# PISCES_200.net
KiCad netlist of a schematic drawn in Altium Designer
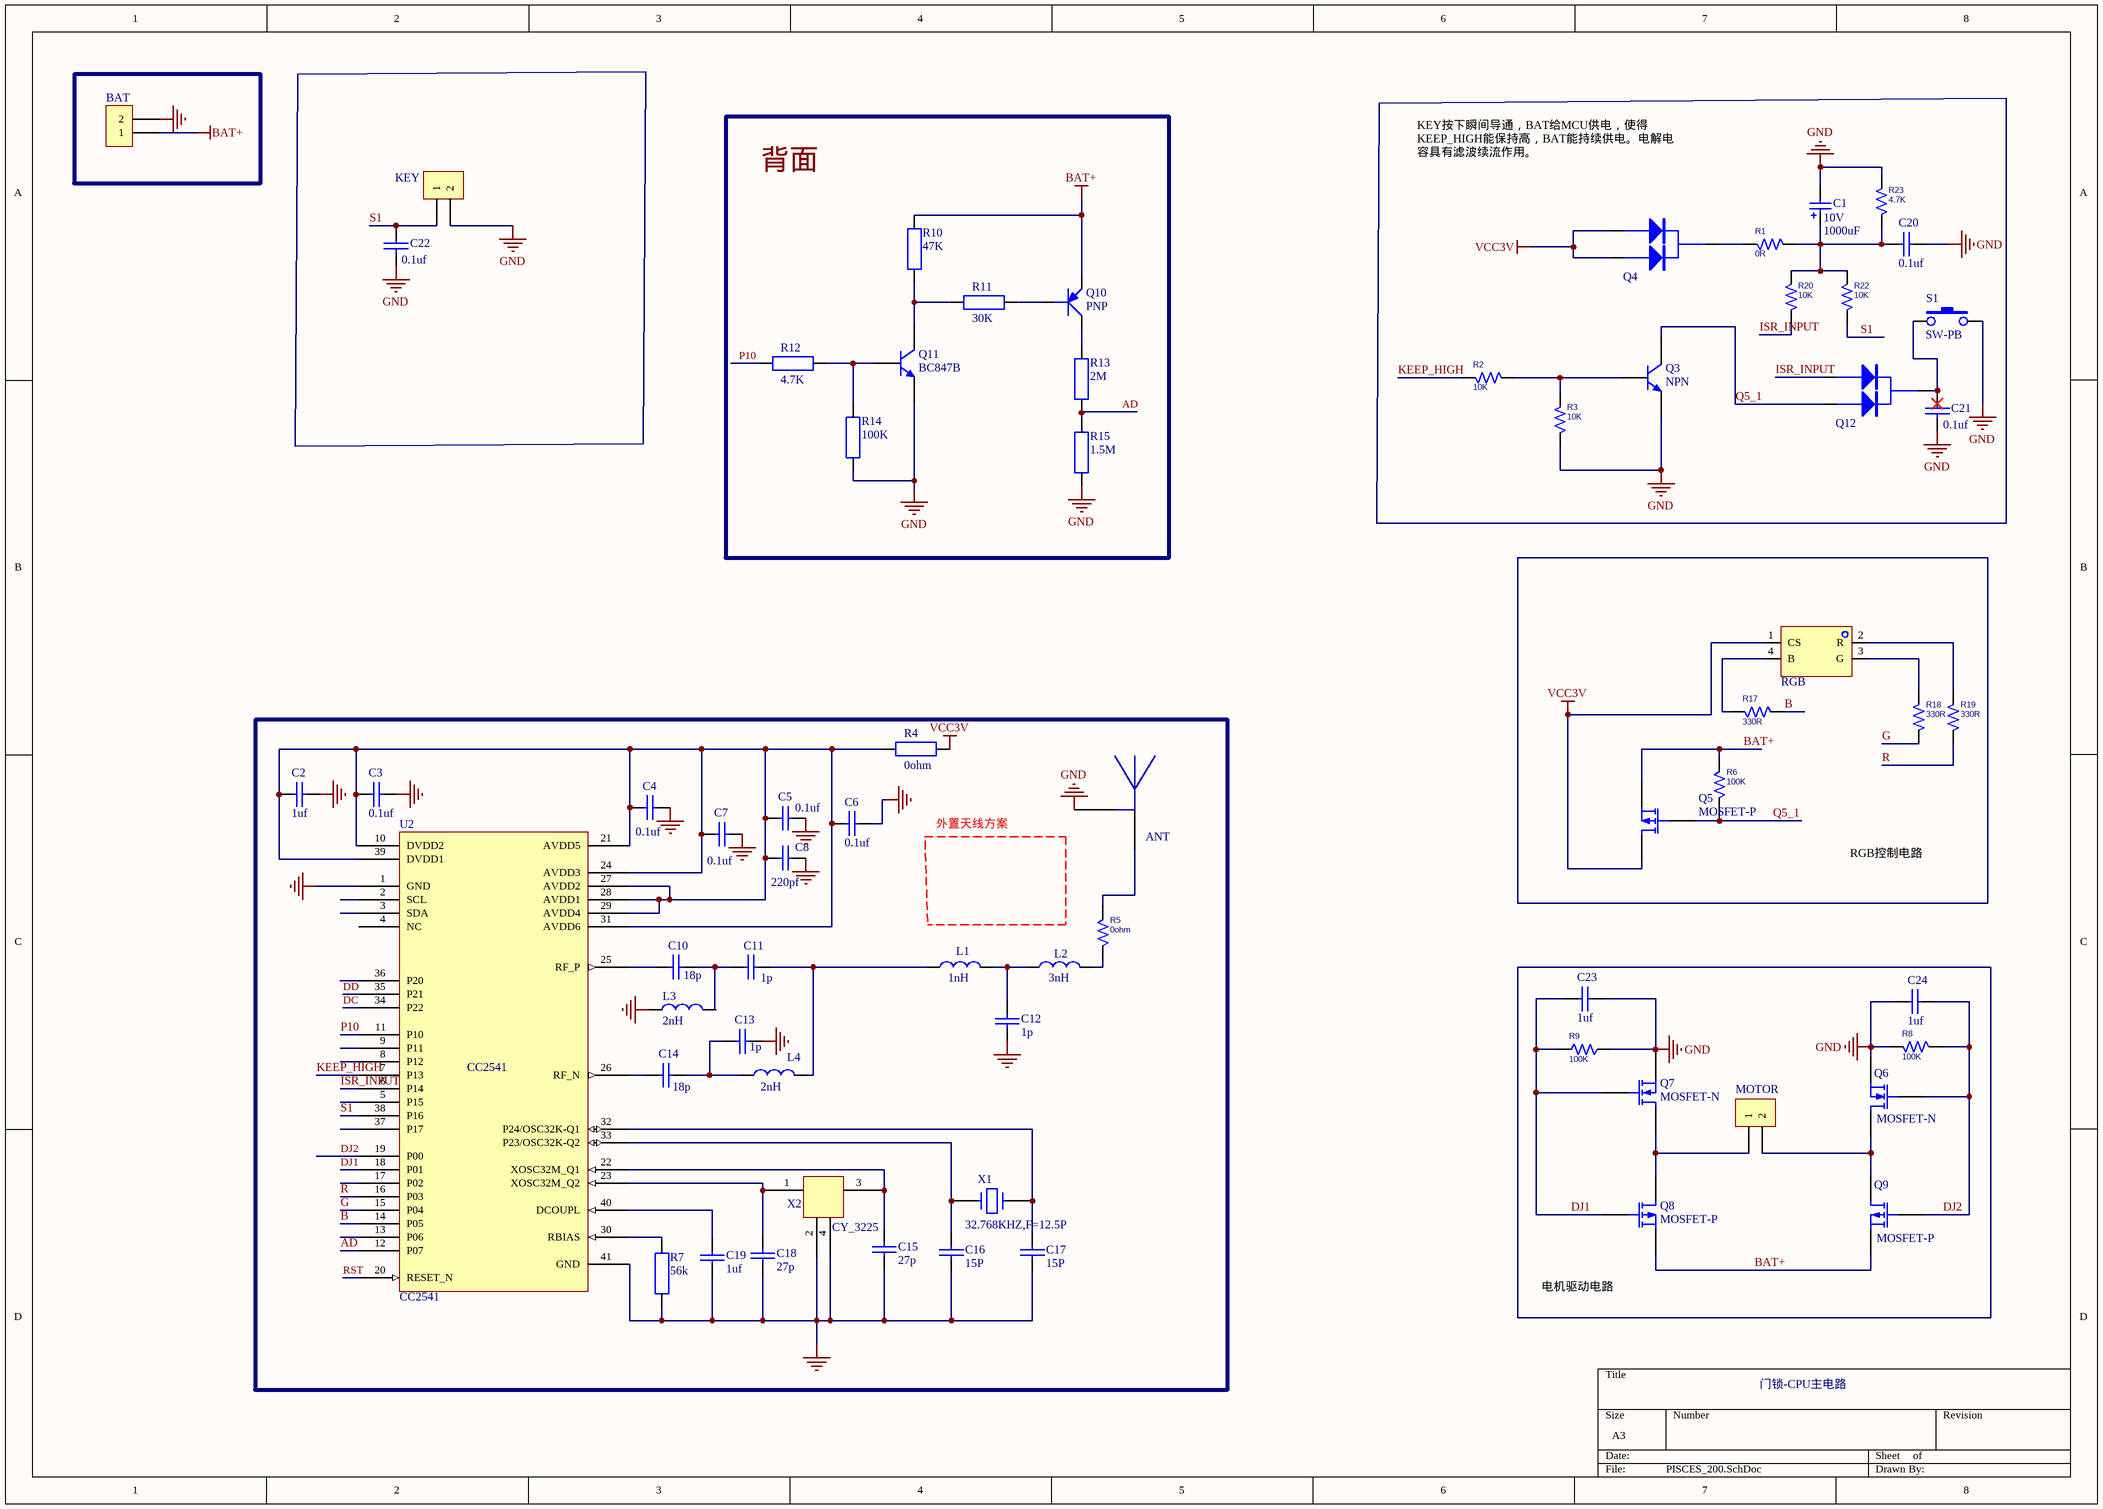
[diagram p0: PISCES_200.SchDoc]

(export (version "E")
  (design (tool "Eeschema 10.0.6"))
  (components
    (comp (ref "ANT") (value "ANT") (footprint "ANT") (libsource (lib "BT100_Project") (part "ANT")))
    (comp (ref "BAT")
      (value "CN1")
      (footprint "2PAD")
      (description "Connector")
      (libsource (lib "") (part "CON2_1"))
    )
    (comp (ref "C1")
      (value "10V")
      (footprint "CAT_ELE")
      (description "Polarized Capacitor (Axial)")
      (fields (field (name "ALTIUM_VALUE") "1000uF") (field (name "PUBLISHER") "Altium Limited"))
      (libsource (lib "Miscellaneous Devices") (part "Cap Pol2"))
    )
    (comp (ref "C2")
      (value "1uf")
      (footprint "PC5-*****-**-0A_0603_TDK")
      (description "PC7-*****-KQA0A")
      (libsource (lib "Schlib") (part "PC7_0402_YAGEO"))
    )
    (comp (ref "C3")
      (value "0.1uf")
      (footprint "PC5-*****-**-0A_0603_TDK")
      (description "PC7-*****-KQA0A")
      (libsource (lib "Schlib") (part "PC7_0402_YAGEO"))
    )
    (comp (ref "C4")
      (value "0.1uf")
      (footprint "PC5-*****-**-0A_0603_TDK")
      (description "PC7-*****-KQA0A")
      (libsource (lib "Schlib") (part "PC7_0402_YAGEO"))
    )
    (comp (ref "C5")
      (value "0.1uf")
      (footprint "PC7-*****-KQA0A_0402_YAGEO")
      (description "PC7-*****-KQA0A")
      (libsource (lib "Schlib") (part "PC7_0402_YAGEO"))
    )
    (comp (ref "C6")
      (value "0.1uf")
      (footprint "PC7-*****-KQA0A_0402_YAGEO")
      (description "PC7-*****-KQA0A")
      (libsource (lib "Schlib") (part "PC7_0402_YAGEO"))
    )
    (comp (ref "C7")
      (value "0.1uf")
      (footprint "PC7-*****-KQA0A_0402_YAGEO")
      (description "PC7-*****-KQA0A")
      (libsource (lib "Schlib") (part "PC7_0402_YAGEO"))
    )
    (comp (ref "C8")
      (value "220pf")
      (footprint "PC7-*****-KQA0A_0402_YAGEO")
      (description "PC7-*****-KQA0A")
      (libsource (lib "Schlib") (part "PC7_0402_YAGEO"))
    )
    (comp (ref "C10")
      (value "18p")
      (footprint "PC7-*****-KQA0A_0402_YAGEO")
      (description "PC7-*****-KQA0A")
      (libsource (lib "Schlib") (part "PC7_0402_YAGEO"))
    )
    (comp (ref "C11")
      (value "1p")
      (footprint "PC7-*****-KQA0A_0402_YAGEO")
      (description "PC7-*****-KQA0A")
      (libsource (lib "Schlib") (part "PC7_0402_YAGEO"))
    )
    (comp (ref "C12")
      (value "1p")
      (footprint "PC7-*****-KQA0A_0402_YAGEO")
      (description "PC7-*****-KQA0A")
      (libsource (lib "Schlib") (part "PC7_0402_YAGEO"))
    )
    (comp (ref "C13")
      (value "1p")
      (footprint "PC7-*****-KQA0A_0402_YAGEO")
      (description "PC7-*****-KQA0A")
      (libsource (lib "Schlib") (part "PC7_0402_YAGEO"))
    )
    (comp (ref "C14")
      (value "18p")
      (footprint "PC7-*****-KQA0A_0402_YAGEO")
      (description "PC7-*****-KQA0A")
      (libsource (lib "Schlib") (part "PC7_0402_YAGEO"))
    )
    (comp (ref "C15")
      (value "27p")
      (footprint "PC7-*****-KO-0A_0603_TDK")
      (description "PC7-*****-KQA0A")
      (libsource (lib "Schlib") (part "PC7_0402_YAGEO"))
    )
    (comp (ref "C16")
      (value "15P")
      (footprint "PC5-*****-**-0A_0603_TDK")
      (description "PC7-*****-KQA0A")
      (libsource (lib "Schlib") (part "PC7_0402_YAGEO"))
    )
    (comp (ref "C17")
      (value "15P")
      (footprint "PC7-*****-KO-0A_0603_TDK")
      (description "PC7-*****-KQA0A")
      (libsource (lib "Schlib") (part "PC7_0402_YAGEO"))
    )
    (comp (ref "C18")
      (value "27p")
      (footprint "PC7-*****-KO-0A_0603_TDK")
      (description "PC7-*****-KQA0A")
      (libsource (lib "Schlib") (part "PC7_0402_YAGEO"))
    )
    (comp (ref "C19")
      (value "1uf")
      (footprint "PC5-*****-**-0A_0603_TDK")
      (description "PC7-*****-KQA0A")
      (libsource (lib "Schlib") (part "PC7_0402_YAGEO"))
    )
    (comp (ref "C20")
      (value "0.1uf")
      (footprint "PC7-*****-KQA0A_0402_YAGEO")
      (description "PC7-*****-KQA0A")
      (libsource (lib "Schlib") (part "PC7_0402_YAGEO"))
    )
    (comp (ref "C21")
      (value "0.1uf")
      (footprint "PC7-*****-KQA0A_0402_YAGEO")
      (description "PC7-*****-KQA0A")
      (libsource (lib "Schlib") (part "PC7_0402_YAGEO"))
    )
    (comp (ref "C22")
      (value "0.1uf")
      (footprint "PC7-*****-KQA0A_0402_YAGEO")
      (description "PC7-*****-KQA0A")
      (libsource (lib "Schlib") (part "PC7_0402_YAGEO"))
    )
    (comp (ref "C23")
      (value "1uf")
      (footprint "PC7-*****-KO-0A_0603_TDK")
      (description "PC7-*****-KQA0A")
      (libsource (lib "Schlib") (part "PC7_0402_YAGEO"))
    )
    (comp (ref "C24")
      (value "1uf")
      (footprint "PC7-*****-KO-0A_0603_TDK")
      (description "PC7-*****-KQA0A")
      (libsource (lib "Schlib") (part "PC7_0402_YAGEO"))
    )
    (comp (ref "KEY")
      (value "CN1")
      (footprint "KEY_2P")
      (description "Connector")
      (libsource (lib "BJC") (part "CON2"))
    )
    (comp (ref "L1")
      (value "1nH")
      (footprint "PC5-*****-**-0A_0402_TDK")
      (description "PWL-00195-00-20")
      (libsource (lib "Schlib") (part "PWL_18nH"))
    )
    (comp (ref "L2")
      (value "3nH")
      (footprint "PC5-*****-**-0A_0402_TDK")
      (description "PWL-00195-00-20")
      (libsource (lib "Schlib") (part "PWL_18nH"))
    )
    (comp (ref "L3")
      (value "2nH")
      (footprint "PC5-*****-**-0A_0402_TDK")
      (description "PWL-00195-00-20")
      (libsource (lib "Schlib") (part "PWL_18nH"))
    )
    (comp (ref "L4")
      (value "2nH")
      (footprint "PC5-*****-**-0A_0402_TDK")
      (description "PWL-00195-00-20")
      (libsource (lib "Schlib") (part "PWL_18nH"))
    )
    (comp (ref "MOTOR")
      (value "CN1")
      (footprint "2PAD")
      (description "Connector")
      (libsource (lib "BJC") (part "CON2"))
    )
    (comp (ref "Q3")
      (value "NPN")
      (footprint "SOT-23")
      (description "BC847C")
      (fields (field (name "PUBLISHER") "Altium Limited"))
      (libsource (lib "PISCES_200") (part "NPN"))
    )
    (comp (ref "Q4") (value "Q4") (footprint "SOT-23") (libsource (lib "PISCES_200") (part "BAT54C")))
    (comp (ref "Q5")
      (value "MOSFET-P")
      (footprint "SOT-23")
      (description "P-Channel MOSFET")
      (fields (field (name "PUBLISHER") "Altium Limited"))
      (libsource (lib "PISCES_200") (part "MOSFET-P"))
    )
    (comp (ref "Q6")
      (value "MOSFET-N")
      (footprint "SOT-23")
      (description "N-Channel MOSFET")
      (fields (field (name "PUBLISHER") "Altium Limited"))
      (libsource (lib "PISCES_200") (part "MOSFET-N"))
    )
    (comp (ref "Q7")
      (value "MOSFET-N")
      (footprint "SOT-23")
      (description "N-Channel MOSFET")
      (fields (field (name "PUBLISHER") "Altium Limited"))
      (libsource (lib "PISCES_200") (part "MOSFET-N"))
    )
    (comp (ref "Q8")
      (value "MOSFET-P")
      (footprint "SOT-23")
      (description "P-Channel MOSFET")
      (fields (field (name "PUBLISHER") "Altium Limited"))
      (libsource (lib "PISCES_200") (part "MOSFET-P"))
    )
    (comp (ref "Q9")
      (value "MOSFET-P")
      (footprint "SOT-23")
      (description "P-Channel MOSFET")
      (fields (field (name "PUBLISHER") "Altium Limited"))
      (libsource (lib "PISCES_200") (part "MOSFET-P"))
    )
    (comp (ref "Q10")
      (value "PNP")
      (footprint "SOT-23")
      (description "BC857C")
      (libsource (lib "PISCES_200") (part "PNP"))
    )
    (comp (ref "Q11")
      (value "BC847B")
      (footprint "SOT-23")
      (description "BC847C")
      (fields (field (name "PUBLISHER") "Altium Limited"))
      (libsource (lib "PISCES_200") (part "NPN"))
    )
    (comp (ref "Q12") (value "Q12") (footprint "SOT-23") (libsource (lib "PISCES_200") (part "BAT54C")))
    (comp (ref "R1")
      (value "0R")
      (footprint "PC7-*****-KQA0A_0402_YAGEO")
      (libsource (lib "*") (part "R_Dup3"))
    )
    (comp (ref "R2")
      (value "10K")
      (footprint "PC7-*****-KQA0A_0402_YAGEO")
      (libsource (lib "*") (part "R_Dup3"))
    )
    (comp (ref "R3")
      (value "10K")
      (footprint "PC7-*****-KQA0A_0402_YAGEO")
      (libsource (lib "*") (part "R_Dup3"))
    )
    (comp (ref "R4")
      (value "0ohm")
      (footprint "PC7-*****-KQA0A_0402_YAGEO")
      (description "PRC-*****-AM-0A_0603")
      (libsource (lib "Schlib") (part "PRC_0603"))
    )
    (comp (ref "R5")
      (value "0ohm")
      (footprint "PC7-*****-KQA0A_0402_YAGEO")
      (libsource (lib "*") (part "R_Dup3"))
    )
    (comp (ref "R6")
      (value "100K")
      (footprint "PC7-*****-KQA0A_0402_YAGEO")
      (libsource (lib "*") (part "R_Dup3"))
    )
    (comp (ref "R7")
      (value "56k")
      (footprint "PRC-*****-BM-0A_0402")
      (description "PRC-*****-AM-0A_0603")
      (libsource (lib "Schlib") (part "PRC_0603"))
    )
    (comp (ref "R8")
      (value "100K")
      (footprint "PC7-*****-KQA0A_0402_YAGEO")
      (libsource (lib "*") (part "R_Dup3"))
    )
    (comp (ref "R9")
      (value "100K")
      (footprint "PC7-*****-KQA0A_0402_YAGEO")
      (libsource (lib "*") (part "R_Dup3"))
    )
    (comp (ref "R10")
      (value "47K")
      (footprint "PISCES_200:PC7-*****-KQA0A_0402_YAGEO")
      (description "PRC-*****-AM-0A_0603")
      (libsource (lib "Schlib") (part "PRC_0603"))
    )
    (comp (ref "R11")
      (value "30K")
      (footprint "PISCES_200:PC7-*****-KQA0A_0402_YAGEO")
      (description "PRC-*****-AM-0A_0603")
      (libsource (lib "Schlib") (part "PRC_0603"))
    )
    (comp (ref "R12")
      (value "4.7K")
      (footprint "PISCES_200:PC7-*****-KQA0A_0402_YAGEO")
      (description "PRC-*****-AM-0A_0603")
      (libsource (lib "Schlib") (part "PRC_0603"))
    )
    (comp (ref "R13")
      (value "2M")
      (footprint "PISCES_200:PC7-*****-KQA0A_0402_YAGEO")
      (description "PRC-*****-AM-0A_0603")
      (libsource (lib "Schlib") (part "PRC_0603"))
    )
    (comp (ref "R14")
      (value "100K")
      (footprint "PISCES_200:PC7-*****-KQA0A_0402_YAGEO")
      (description "PRC-*****-AM-0A_0603")
      (libsource (lib "Schlib") (part "PRC_0603"))
    )
    (comp (ref "R15")
      (value "1.5M")
      (footprint "PISCES_200:PC7-*****-KQA0A_0402_YAGEO")
      (description "PRC-*****-AM-0A_0603")
      (libsource (lib "Schlib") (part "PRC_0603"))
    )
    (comp (ref "R17")
      (value "330R")
      (footprint "PC7-*****-KQA0A_0402_YAGEO")
      (libsource (lib "*") (part "R_Dup3"))
    )
    (comp (ref "R18")
      (value "330R")
      (footprint "PC7-*****-KQA0A_0402_YAGEO")
      (libsource (lib "*") (part "R_Dup3"))
    )
    (comp (ref "R19")
      (value "330R")
      (footprint "PC7-*****-KQA0A_0402_YAGEO")
      (libsource (lib "*") (part "R_Dup3"))
    )
    (comp (ref "R20")
      (value "10K")
      (footprint "PC7-*****-KQA0A_0402_YAGEO")
      (libsource (lib "*") (part "R_Dup3"))
    )
    (comp (ref "R22")
      (value "10K")
      (footprint "PC7-*****-KQA0A_0402_YAGEO")
      (libsource (lib "*") (part "R_Dup3"))
    )
    (comp (ref "R23")
      (value "4.7K")
      (footprint "PC7-*****-KQA0A_0402_YAGEO")
      (libsource (lib "*") (part "R_Dup3"))
    )
    (comp (ref "RGB") (value "RGB") (libsource (lib "PISCES_200") (part "RGB")))
    (comp (ref "S1") (value "SW-PB") (footprint "TS-030") (libsource (lib "LG_SCH") (part "SW-PB")))
    (comp (ref "U2") (value "CC2541") (footprint "CC2530_QFN40") (libsource (lib "*") (part "CC2541")))
    (comp (ref "X1")
      (value "32.768KHZ,F=12.5P")
      (footprint "FC-135")
      (description "Crystal")
      (libsource (lib "CC254xEM原理图库") (part "CRYSTAL"))
    )
    (comp (ref "X2")
      (value "CY_3225")
      (footprint "CY_3225")
      (libsource (lib "CC254xEM原理图库") (part "CY_3225"))
    )
  )
  (nets
    (net (code "1") (name "/AD") (class "Default")
      (node (ref "R13") (pin "1") (pinfunction "1_1") (pintype "passive"))
      (node (ref "R15") (pin "2") (pinfunction "2_2") (pintype "passive"))
      (node (ref "U2") (pin "12") (pinfunction "P07_12") (pintype "passive"))
    )
    (net (code "2") (name "/B") (class "Default")
      (node (ref "R17") (pin "2") (pinfunction "2_2") (pintype "passive"))
      (node (ref "U2") (pin "14") (pinfunction "P05_14") (pintype "passive"))
    )
    (net (code "3") (name "/DC") (class "Default")
      (node (ref "U2") (pin "34") (pinfunction "P22_34") (pintype "passive"))
    )
    (net (code "4") (name "/DD") (class "Default")
      (node (ref "U2") (pin "35") (pinfunction "P21_35") (pintype "passive"))
    )
    (net (code "5") (name "/DJ1") (class "Default")
      (node (ref "C23") (pin "1") (pinfunction "1_1") (pintype "passive"))
      (node (ref "Q7") (pin "1") (pinfunction "G_1") (pintype "passive"))
      (node (ref "Q8") (pin "1") (pinfunction "G_1") (pintype "passive"))
      (node (ref "R9") (pin "1") (pinfunction "1_1") (pintype "passive"))
      (node (ref "U2") (pin "18") (pinfunction "P01_18") (pintype "passive"))
    )
    (net (code "6") (name "/DJ2") (class "Default")
      (node (ref "C24") (pin "2") (pinfunction "2_2") (pintype "passive"))
      (node (ref "Q6") (pin "1") (pinfunction "G_1") (pintype "passive"))
      (node (ref "Q9") (pin "1") (pinfunction "G_1") (pintype "passive"))
      (node (ref "R8") (pin "1") (pinfunction "1_1") (pintype "passive"))
      (node (ref "U2") (pin "19") (pinfunction "P00_19") (pintype "passive"))
    )
    (net (code "7") (name "/G") (class "Default")
      (node (ref "R18") (pin "2") (pinfunction "2_2") (pintype "passive"))
      (node (ref "U2") (pin "15") (pinfunction "P04_15") (pintype "passive"))
    )
    (net (code "8") (name "/ISR_INPUT") (class "Default")
      (node (ref "Q12") (pin "1") (pinfunction "1_1") (pintype "passive"))
      (node (ref "R20") (pin "1") (pinfunction "1_1") (pintype "passive"))
      (node (ref "U2") (pin "6") (pinfunction "P14_6") (pintype "passive"))
    )
    (net (code "9") (name "/KEEP_HIGH") (class "Default")
      (node (ref "R2") (pin "1") (pinfunction "1_1") (pintype "passive"))
      (node (ref "U2") (pin "7") (pinfunction "P13_7") (pintype "passive"))
    )
    (net (code "10") (name "/P10") (class "Default")
      (node (ref "R12") (pin "1") (pinfunction "1_1") (pintype "passive"))
      (node (ref "U2") (pin "11") (pinfunction "P10_11") (pintype "passive"))
    )
    (net (code "11") (name "/Q5_1") (class "Default")
      (node (ref "Q12") (pin "2") (pinfunction "2_2") (pintype "passive"))
      (node (ref "Q3") (pin "3") (pinfunction "3_3") (pintype "passive"))
      (node (ref "Q5") (pin "1") (pinfunction "G_1") (pintype "passive"))
      (node (ref "R6") (pin "2") (pinfunction "2_2") (pintype "passive"))
    )
    (net (code "12") (name "/R") (class "Default")
      (node (ref "R19") (pin "2") (pinfunction "2_2") (pintype "passive"))
      (node (ref "U2") (pin "16") (pinfunction "P03_16") (pintype "passive"))
    )
    (net (code "13") (name "/RST") (class "Default")
      (node (ref "U2") (pin "20") (pinfunction "RESET_N_20") (pintype "input"))
    )
    (net (code "14") (name "/S1") (class "Default")
      (node (ref "C22") (pin "1") (pinfunction "1_1") (pintype "passive"))
      (node (ref "KEY") (pin "1") (pinfunction "1_1") (pintype "passive"))
      (node (ref "R22") (pin "1") (pinfunction "1_1") (pintype "passive"))
      (node (ref "U2") (pin "38") (pinfunction "P16_38") (pintype "passive"))
    )
    (net (code "16") (name "BAT+") (class "Default")
      (node (ref "BAT") (pin "1") (pinfunction "1_1") (pintype "passive"))
      (node (ref "Q10") (pin "2") (pinfunction "2_2") (pintype "passive"))
      (node (ref "Q5") (pin "2") (pinfunction "S_2") (pintype "passive"))
      (node (ref "Q8") (pin "2") (pinfunction "S_2") (pintype "passive"))
      (node (ref "Q9") (pin "2") (pinfunction "S_2") (pintype "passive"))
      (node (ref "R10") (pin "2") (pinfunction "2_2") (pintype "passive"))
      (node (ref "R6") (pin "1") (pinfunction "1_1") (pintype "passive"))
    )
    (net (code "17") (name "GND") (class "Default")
      (node (ref "ANT") (pin "2") (pinfunction "2_2") (pintype "passive"))
      (node (ref "BAT") (pin "2") (pinfunction "2_2") (pintype "passive"))
      (node (ref "C1") (pin "2") (pinfunction "2_2") (pintype "passive"))
      (node (ref "C12") (pin "1") (pinfunction "1_1") (pintype "passive"))
      (node (ref "C13") (pin "2") (pinfunction "2_2") (pintype "passive"))
      (node (ref "C15") (pin "1") (pinfunction "1_1") (pintype "passive"))
      (node (ref "C16") (pin "1") (pinfunction "1_1") (pintype "passive"))
      (node (ref "C17") (pin "1") (pinfunction "1_1") (pintype "passive"))
      (node (ref "C18") (pin "1") (pinfunction "1_1") (pintype "passive"))
      (node (ref "C19") (pin "1") (pinfunction "1_1") (pintype "passive"))
      (node (ref "C2") (pin "2") (pinfunction "2_2") (pintype "passive"))
      (node (ref "C20") (pin "2") (pinfunction "2_2") (pintype "passive"))
      (node (ref "C21") (pin "2") (pinfunction "2_2") (pintype "passive"))
      (node (ref "C22") (pin "2") (pinfunction "2_2") (pintype "passive"))
      (node (ref "C23") (pin "2") (pinfunction "2_2") (pintype "passive"))
      (node (ref "C24") (pin "1") (pinfunction "1_1") (pintype "passive"))
      (node (ref "C3") (pin "2") (pinfunction "2_2") (pintype "passive"))
      (node (ref "C4") (pin "2") (pinfunction "2_2") (pintype "passive"))
      (node (ref "C5") (pin "2") (pinfunction "2_2") (pintype "passive"))
      (node (ref "C6") (pin "2") (pinfunction "2_2") (pintype "passive"))
      (node (ref "C7") (pin "2") (pinfunction "2_2") (pintype "passive"))
      (node (ref "C8") (pin "1") (pinfunction "1_1") (pintype "passive"))
      (node (ref "KEY") (pin "2") (pinfunction "2_2") (pintype "passive"))
      (node (ref "L3") (pin "1") (pintype "passive"))
      (node (ref "Q11") (pin "2") (pinfunction "2_2") (pintype "passive"))
      (node (ref "Q3") (pin "2") (pinfunction "2_2") (pintype "passive"))
      (node (ref "Q6") (pin "2") (pinfunction "S_2") (pintype "passive"))
      (node (ref "Q7") (pin "2") (pinfunction "S_2") (pintype "passive"))
      (node (ref "R14") (pin "1") (pinfunction "1_1") (pintype "passive"))
      (node (ref "R15") (pin "1") (pinfunction "1_1") (pintype "passive"))
      (node (ref "R23") (pin "2") (pinfunction "2_2") (pintype "passive"))
      (node (ref "R3") (pin "2") (pinfunction "2_2") (pintype "passive"))
      (node (ref "R7") (pin "2") (pinfunction "2_2") (pintype "passive"))
      (node (ref "R8") (pin "2") (pinfunction "2_2") (pintype "passive"))
      (node (ref "R9") (pin "2") (pinfunction "2_2") (pintype "passive"))
      (node (ref "S1") (pin "2") (pinfunction "2_2") (pintype "passive"))
      (node (ref "U2") (pin "1") (pinfunction "GND_1") (pintype "power_in"))
      (node (ref "U2") (pin "41") (pinfunction "GND_41") (pintype "power_in"))
      (node (ref "X2") (pin "2") (pinfunction "2_2") (pintype "power_in"))
      (node (ref "X2") (pin "4") (pinfunction "4_4") (pintype "power_in"))
    )
    (net (code "18") (name "Net-(ANT-Pad1)") (class "Default")
      (node (ref "ANT") (pin "1") (pinfunction "1_1") (pintype "passive"))
      (node (ref "R5") (pin "1") (pinfunction "1_1") (pintype "passive"))
    )
    (net (code "19") (name "Net-(C1-Pad1)") (class "Default")
      (node (ref "C1") (pin "1") (pinfunction "1_1") (pintype "passive"))
      (node (ref "C20") (pin "1") (pinfunction "1_1") (pintype "passive"))
      (node (ref "R1") (pin "2") (pinfunction "2_2") (pintype "passive"))
      (node (ref "R20") (pin "2") (pinfunction "2_2") (pintype "passive"))
      (node (ref "R22") (pin "2") (pinfunction "2_2") (pintype "passive"))
      (node (ref "R23") (pin "1") (pinfunction "1_1") (pintype "passive"))
    )
    (net (code "20") (name "Net-(C10-Pad2)") (class "Default")
      (node (ref "C10") (pin "2") (pinfunction "2_2") (pintype "passive"))
      (node (ref "C11") (pin "1") (pinfunction "1_1") (pintype "passive"))
      (node (ref "L3") (pin "2") (pintype "passive"))
    )
    (net (code "21") (name "Net-(C11-Pad2)") (class "Default")
      (node (ref "C11") (pin "2") (pinfunction "2_2") (pintype "passive"))
      (node (ref "L1") (pin "1") (pintype "passive"))
      (node (ref "L4") (pin "2") (pintype "passive"))
    )
    (net (code "22") (name "Net-(C12-Pad2)") (class "Default")
      (node (ref "C12") (pin "2") (pinfunction "2_2") (pintype "passive"))
      (node (ref "L1") (pin "2") (pintype "passive"))
      (node (ref "L2") (pin "1") (pintype "passive"))
    )
    (net (code "23") (name "Net-(C13-Pad1)") (class "Default")
      (node (ref "C13") (pin "1") (pinfunction "1_1") (pintype "passive"))
      (node (ref "C14") (pin "2") (pinfunction "2_2") (pintype "passive"))
      (node (ref "L4") (pin "1") (pintype "passive"))
    )
    (net (code "24") (name "Net-(C21-Pad1)") (class "Default")
      (node (ref "C21") (pin "1") (pinfunction "1_1") (pintype "passive"))
      (node (ref "Q12") (pin "3") (pinfunction "3_3") (pintype "passive"))
      (node (ref "S1") (pin "1") (pinfunction "1_1") (pintype "passive"))
    )
    (net (code "25") (name "Net-(L2-Pad2)") (class "Default")
      (node (ref "L2") (pin "2") (pintype "passive"))
      (node (ref "R5") (pin "2") (pinfunction "2_2") (pintype "passive"))
    )
    (net (code "26") (name "Net-(Q3-Pad1)") (class "Default")
      (node (ref "Q3") (pin "1") (pinfunction "1_1") (pintype "passive"))
      (node (ref "R2") (pin "2") (pinfunction "2_2") (pintype "passive"))
      (node (ref "R3") (pin "1") (pinfunction "1_1") (pintype "passive"))
    )
    (net (code "27") (name "Net-(Q4-Pad3)") (class "Default")
      (node (ref "Q4") (pin "3") (pinfunction "3_3") (pintype "passive"))
      (node (ref "R1") (pin "1") (pinfunction "1_1") (pintype "passive"))
    )
    (net (code "28") (name "Net-(Q6-D)") (class "Default")
      (node (ref "MOTOR") (pin "2") (pinfunction "2_2") (pintype "passive"))
      (node (ref "Q6") (pin "3") (pinfunction "D_3") (pintype "passive"))
      (node (ref "Q9") (pin "3") (pinfunction "D_3") (pintype "passive"))
    )
    (net (code "29") (name "Net-(Q7-D)") (class "Default")
      (node (ref "MOTOR") (pin "1") (pinfunction "1_1") (pintype "passive"))
      (node (ref "Q7") (pin "3") (pinfunction "D_3") (pintype "passive"))
      (node (ref "Q8") (pin "3") (pinfunction "D_3") (pintype "passive"))
    )
    (net (code "30") (name "Net-(Q10-Pad1)") (class "Default")
      (node (ref "Q10") (pin "1") (pinfunction "1_1") (pintype "passive"))
      (node (ref "R11") (pin "2") (pinfunction "2_2") (pintype "passive"))
    )
    (net (code "31") (name "Net-(Q10-Pad3)") (class "Default")
      (node (ref "Q10") (pin "3") (pinfunction "3_3") (pintype "passive"))
      (node (ref "R13") (pin "2") (pinfunction "2_2") (pintype "passive"))
    )
    (net (code "32") (name "Net-(Q11-Pad1)") (class "Default")
      (node (ref "Q11") (pin "1") (pinfunction "1_1") (pintype "passive"))
      (node (ref "R12") (pin "2") (pinfunction "2_2") (pintype "passive"))
      (node (ref "R14") (pin "2") (pinfunction "2_2") (pintype "passive"))
    )
    (net (code "33") (name "Net-(Q11-Pad3)") (class "Default")
      (node (ref "Q11") (pin "3") (pinfunction "3_3") (pintype "passive"))
      (node (ref "R10") (pin "1") (pinfunction "1_1") (pintype "passive"))
      (node (ref "R11") (pin "1") (pinfunction "1_1") (pintype "passive"))
    )
    (net (code "34") (name "Net-(RGB-B)") (class "Default")
      (node (ref "R17") (pin "1") (pinfunction "1_1") (pintype "passive"))
      (node (ref "RGB") (pin "4") (pinfunction "B_4") (pintype "passive"))
    )
    (net (code "35") (name "Net-(RGB-G)") (class "Default")
      (node (ref "R18") (pin "1") (pinfunction "1_1") (pintype "passive"))
      (node (ref "RGB") (pin "3") (pinfunction "G_3") (pintype "passive"))
    )
    (net (code "36") (name "Net-(RGB-R)") (class "Default")
      (node (ref "R19") (pin "1") (pinfunction "1_1") (pintype "passive"))
      (node (ref "RGB") (pin "2") (pinfunction "R_2") (pintype "passive"))
    )
    (net (code "37") (name "Net-(U2-AVDD1)") (class "Default")
      (node (ref "C2") (pin "1") (pinfunction "1_1") (pintype "passive"))
      (node (ref "C3") (pin "1") (pinfunction "1_1") (pintype "passive"))
      (node (ref "C4") (pin "1") (pinfunction "1_1") (pintype "passive"))
      (node (ref "C5") (pin "1") (pinfunction "1_1") (pintype "passive"))
      (node (ref "C6") (pin "1") (pinfunction "1_1") (pintype "passive"))
      (node (ref "C7") (pin "1") (pinfunction "1_1") (pintype "passive"))
      (node (ref "C8") (pin "2") (pinfunction "2_2") (pintype "passive"))
      (node (ref "R4") (pin "1") (pinfunction "1_1") (pintype "passive"))
      (node (ref "U2") (pin "10") (pinfunction "DVDD2_10") (pintype "power_in"))
      (node (ref "U2") (pin "21") (pinfunction "AVDD5_21") (pintype "power_in"))
      (node (ref "U2") (pin "24") (pinfunction "AVDD3_24") (pintype "power_in"))
      (node (ref "U2") (pin "27") (pinfunction "AVDD2_27") (pintype "power_in"))
      (node (ref "U2") (pin "28") (pinfunction "AVDD1_28") (pintype "power_in"))
      (node (ref "U2") (pin "29") (pinfunction "AVDD4_29") (pintype "power_in"))
      (node (ref "U2") (pin "31") (pinfunction "AVDD6_31") (pintype "power_in"))
      (node (ref "U2") (pin "39") (pinfunction "DVDD1_39") (pintype "power_in"))
    )
    (net (code "38") (name "Net-(U2-DCOUPL)") (class "Default")
      (node (ref "C19") (pin "2") (pinfunction "2_2") (pintype "passive"))
      (node (ref "U2") (pin "40") (pinfunction "DCOUPL_40") (pintype "input"))
    )
    (net (code "39") (name "Net-(U2-P23{slash}OSC32K-Q2)") (class "Default")
      (node (ref "C16") (pin "2") (pinfunction "2_2") (pintype "passive"))
      (node (ref "U2") (pin "33") (pinfunction "P23/OSC32K-Q2_33") (pintype "bidirectional"))
      (node (ref "X1") (pin "1") (pinfunction "1_1") (pintype "passive"))
    )
    (net (code "40") (name "Net-(U2-P24{slash}OSC32K-Q1)") (class "Default")
      (node (ref "C17") (pin "2") (pinfunction "2_2") (pintype "passive"))
      (node (ref "U2") (pin "32") (pinfunction "P24/OSC32K-Q1_32") (pintype "bidirectional"))
      (node (ref "X1") (pin "2") (pinfunction "2_2") (pintype "passive"))
    )
    (net (code "41") (name "Net-(U2-RBIAS)") (class "Default")
      (node (ref "R7") (pin "1") (pinfunction "1_1") (pintype "passive"))
      (node (ref "U2") (pin "30") (pinfunction "RBIAS_30") (pintype "input"))
    )
    (net (code "42") (name "Net-(U2-RF_N)") (class "Default")
      (node (ref "C14") (pin "1") (pinfunction "1_1") (pintype "passive"))
      (node (ref "U2") (pin "26") (pinfunction "RF_N_26") (pintype "output"))
    )
    (net (code "43") (name "Net-(U2-RF_P)") (class "Default")
      (node (ref "C10") (pin "1") (pinfunction "1_1") (pintype "passive"))
      (node (ref "U2") (pin "25") (pinfunction "RF_P_25") (pintype "output"))
    )
    (net (code "44") (name "Net-(U2-XOSC32M_Q1)") (class "Default")
      (node (ref "C15") (pin "2") (pinfunction "2_2") (pintype "passive"))
      (node (ref "U2") (pin "22") (pinfunction "XOSC32M_Q1_22") (pintype "input"))
      (node (ref "X2") (pin "3") (pinfunction "3_3") (pintype "power_in"))
    )
    (net (code "45") (name "Net-(U2-XOSC32M_Q2)") (class "Default")
      (node (ref "C18") (pin "2") (pinfunction "2_2") (pintype "passive"))
      (node (ref "U2") (pin "23") (pinfunction "XOSC32M_Q2_23") (pintype "input"))
      (node (ref "X2") (pin "1") (pinfunction "1_1") (pintype "power_in"))
    )
    (net (code "46") (name "VCC3V") (class "Default")
      (node (ref "Q4") (pin "1") (pinfunction "1_1") (pintype "passive"))
      (node (ref "Q4") (pin "2") (pinfunction "2_2") (pintype "passive"))
      (node (ref "Q5") (pin "3") (pinfunction "D_3") (pintype "passive"))
      (node (ref "R4") (pin "2") (pinfunction "2_2") (pintype "passive"))
      (node (ref "RGB") (pin "1") (pinfunction "CS_1") (pintype "passive"))
    )
    (net (code "47") (name "unconnected-(U2-NC-Pad4)") (class "Default")
      (node (ref "U2") (pin "4") (pinfunction "NC_4") (pintype "power_in"))
    )
    (net (code "48") (name "unconnected-(U2-P02-Pad17)") (class "Default")
      (node (ref "U2") (pin "17") (pinfunction "P02_17") (pintype "passive"))
    )
    (net (code "49") (name "unconnected-(U2-P06-Pad13)") (class "Default")
      (node (ref "U2") (pin "13") (pinfunction "P06_13") (pintype "passive"))
    )
    (net (code "50") (name "unconnected-(U2-P11-Pad9)") (class "Default")
      (node (ref "U2") (pin "9") (pinfunction "P11_9") (pintype "passive"))
    )
    (net (code "51") (name "unconnected-(U2-P12-Pad8)") (class "Default")
      (node (ref "U2") (pin "8") (pinfunction "P12_8") (pintype "passive"))
    )
    (net (code "52") (name "unconnected-(U2-P15-Pad5)") (class "Default")
      (node (ref "U2") (pin "5") (pinfunction "P15_5") (pintype "passive"))
    )
    (net (code "53") (name "unconnected-(U2-P17-Pad37)") (class "Default")
      (node (ref "U2") (pin "37") (pinfunction "P17_37") (pintype "passive"))
    )
    (net (code "54") (name "unconnected-(U2-P20-Pad36)") (class "Default")
      (node (ref "U2") (pin "36") (pinfunction "P20_36") (pintype "passive"))
    )
    (net (code "55") (name "unconnected-(U2-SCL-Pad2)") (class "Default")
      (node (ref "U2") (pin "2") (pinfunction "SCL_2") (pintype "power_in"))
    )
    (net (code "56") (name "unconnected-(U2-SDA-Pad3)") (class "Default")
      (node (ref "U2") (pin "3") (pinfunction "SDA_3") (pintype "power_in"))
    )
  )
)
